# 04_ZYNQ_BANK0.net
KiCad netlist of a schematic drawn in Altium Designer
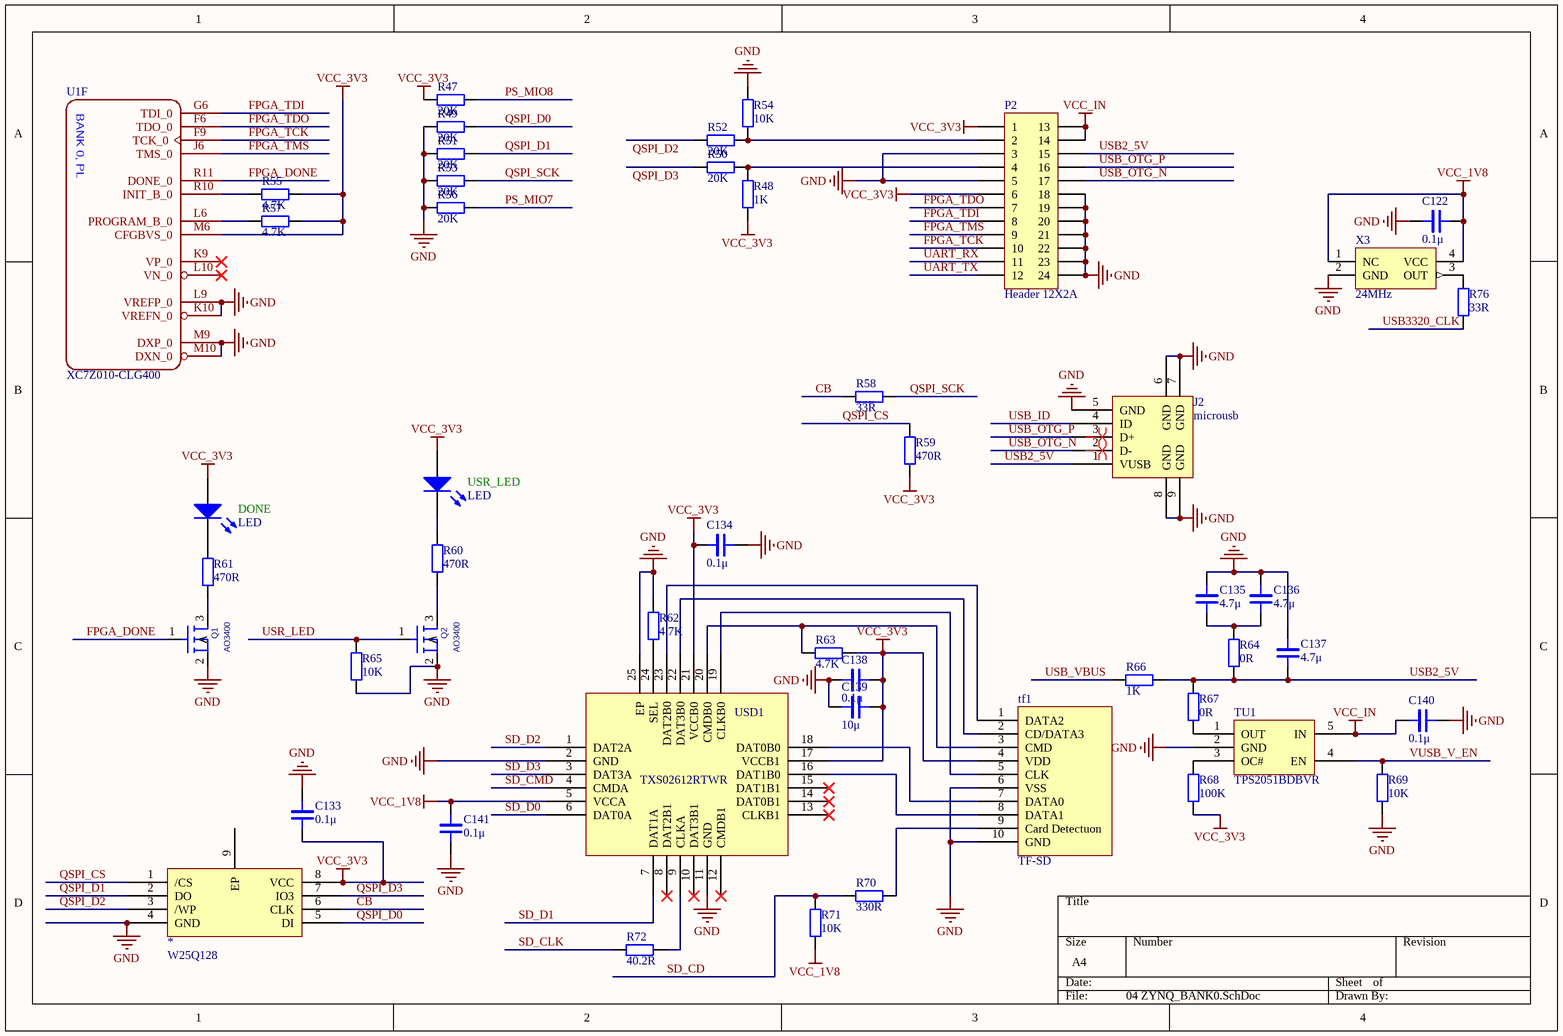
[diagram p0: 04 ZYNQ_BANK0.SchDoc]

(export (version "E")
  (design (tool "Eeschema 10.0.6"))
  (components
    (comp (ref "*") (value "W25Q128") (footprint "W25Q256") (libsource (lib "Schlib1") (part "W25Q128")))
    (comp (ref "C122")
      (value "0.1μ")
      (footprint "LC-0402_C")
      (description "Capacitor")
      (libsource (lib "DDR3_xc7z010-clg400") (part "CAP_2"))
    )
    (comp (ref "C133")
      (value "0.1μ")
      (footprint "LC-0402_C")
      (description "Capacitor")
      (libsource (lib "DDR3_xc7z010-clg400") (part "CAP_2"))
    )
    (comp (ref "C134")
      (value "0.1μ")
      (footprint "LC-0402_C")
      (description "Capacitor")
      (libsource (lib "DDR3_xc7z010-clg400") (part "CAP_2"))
    )
    (comp (ref "C135")
      (value "4.7μ")
      (footprint "LC-0402_C")
      (description "Capacitor")
      (libsource (lib "DDR3_xc7z010-clg400") (part "CAP_2"))
    )
    (comp (ref "C136")
      (value "4.7μ")
      (footprint "LC-0402_C")
      (description "Capacitor")
      (libsource (lib "DDR3_xc7z010-clg400") (part "CAP_2"))
    )
    (comp (ref "C137")
      (value "4.7μ")
      (footprint "LC-0402_C")
      (description "Capacitor")
      (libsource (lib "DDR3_xc7z010-clg400") (part "CAP_2"))
    )
    (comp (ref "C138")
      (value "0.1μ")
      (footprint "LC-0402_C")
      (description "Capacitor")
      (libsource (lib "DDR3_xc7z010-clg400") (part "CAP_2"))
    )
    (comp (ref "C139")
      (value "10μ")
      (footprint "LC-0402_C")
      (description "Capacitor")
      (libsource (lib "DDR3_xc7z010-clg400") (part "CAP_2"))
    )
    (comp (ref "C140")
      (value "0.1μ")
      (footprint "LC-0402_C")
      (description "Capacitor")
      (libsource (lib "DDR3_xc7z010-clg400") (part "CAP_2"))
    )
    (comp (ref "C141")
      (value "0.1μ")
      (footprint "LC-0402_C")
      (description "Capacitor")
      (libsource (lib "DDR3_xc7z010-clg400") (part "CAP_2"))
    )
    (comp (ref "DONE")
      (value "LED")
      (footprint "D0402")
      (description "Typical INFRARED GaAs LED")
      (fields (field (name "PUBLISHER") "Altium Limited"))
      (libsource (lib "Miscellaneous Devices") (part "LED0"))
    )
    (comp (ref "J2")
      (value "microusb")
      (footprint "micro usb")
      (libsource (lib "AD9363_ZYNQ_V2") (part "microusb"))
    )
    (comp (ref "P2")
      (value "Header 12X2A")
      (footprint "HDR2X12_CEN")
      (description "Header, 12-Pin, Dual row")
      (fields (field (name "PUBLISHER") "Altium Limited"))
      (libsource (lib "Miscellaneous Connectors") (part "Header 12X2A"))
    )
    (comp (ref "Q1") (value "AO3400") (footprint "NMOS") (libsource (lib "ZYNQ领航者底板") (part "AO3400")))
    (comp (ref "Q2") (value "AO3400") (footprint "NMOS") (libsource (lib "ZYNQ领航者底板") (part "AO3400")))
    (comp (ref "R47")
      (value "20K")
      (footprint "LC-0402_R")
      (description "Resistor")
      (libsource (lib "") (part "RES_1"))
    )
    (comp (ref "R48")
      (value "1K")
      (footprint "LC-0402_R")
      (description "Resistor")
      (libsource (lib "") (part "RES_3"))
    )
    (comp (ref "R49")
      (value "20K")
      (footprint "LC-0402_R")
      (description "Resistor")
      (libsource (lib "") (part "RES_1"))
    )
    (comp (ref "R50")
      (value "20K")
      (footprint "LC-0402_R")
      (description "Resistor")
      (libsource (lib "") (part "RES_2"))
    )
    (comp (ref "R51")
      (value "20K")
      (footprint "LC-0402_R")
      (description "Resistor")
      (libsource (lib "") (part "RES_1"))
    )
    (comp (ref "R52")
      (value "20K")
      (footprint "LC-0402_R")
      (description "Resistor")
      (libsource (lib "") (part "RES_2"))
    )
    (comp (ref "R53")
      (value "20K")
      (footprint "LC-0402_R")
      (description "Resistor")
      (libsource (lib "") (part "RES_1"))
    )
    (comp (ref "R54")
      (value "10K")
      (footprint "LC-0402_R")
      (description "Resistor")
      (libsource (lib "") (part "RES_3"))
    )
    (comp (ref "R55")
      (value "4.7K")
      (footprint "LC-0402_R")
      (description "Resistor")
      (libsource (lib "") (part "RES_2"))
    )
    (comp (ref "R56")
      (value "20K")
      (footprint "LC-0402_R")
      (description "Resistor")
      (libsource (lib "") (part "RES_1"))
    )
    (comp (ref "R57")
      (value "4.7K")
      (footprint "LC-0402_R")
      (description "Resistor")
      (libsource (lib "") (part "RES_2"))
    )
    (comp (ref "R58")
      (value "33R")
      (footprint "LC-0402_R")
      (description "Resistor")
      (libsource (lib "") (part "RES_1"))
    )
    (comp (ref "R59")
      (value "470R")
      (footprint "LC-0402_R")
      (description "Resistor")
      (libsource (lib "DDR3_xc7z010-clg400") (part "RES"))
    )
    (comp (ref "R60")
      (value "470R")
      (footprint "LC-0402_R")
      (description "Resistor")
      (libsource (lib "") (part "RES_3"))
    )
    (comp (ref "R61")
      (value "470R")
      (footprint "LC-0402_R")
      (description "Resistor")
      (libsource (lib "") (part "RES_3"))
    )
    (comp (ref "R62")
      (value "4.7K")
      (footprint "LC-0402_R")
      (description "Resistor")
      (libsource (lib "DDR3_xc7z010-clg400") (part "RES"))
    )
    (comp (ref "R63")
      (value "4.7K")
      (footprint "LC-0402_R")
      (description "Resistor")
      (libsource (lib "") (part "RES_2"))
    )
    (comp (ref "R64")
      (value "0R")
      (footprint "LC-0402_R")
      (description "Resistor")
      (libsource (lib "DDR3_xc7z010-clg400") (part "RES"))
    )
    (comp (ref "R65")
      (value "10K")
      (footprint "LC-0402_R")
      (description "Resistor")
      (libsource (lib "DDR3_xc7z010-clg400") (part "RES"))
    )
    (comp (ref "R66")
      (value "1K")
      (footprint "LC-0402_R")
      (description "Resistor")
      (libsource (lib "") (part "RES_2"))
    )
    (comp (ref "R67")
      (value "0R")
      (footprint "LC-0402_R")
      (description "Resistor")
      (libsource (lib "DDR3_xc7z010-clg400") (part "RES"))
    )
    (comp (ref "R68")
      (value "100K")
      (footprint "LC-0402_R")
      (description "Resistor")
      (libsource (lib "DDR3_xc7z010-clg400") (part "RES"))
    )
    (comp (ref "R69")
      (value "10K")
      (footprint "LC-0402_R")
      (description "Resistor")
      (libsource (lib "DDR3_xc7z010-clg400") (part "RES"))
    )
    (comp (ref "R70")
      (value "330R")
      (footprint "LC-0402_R")
      (description "Resistor")
      (libsource (lib "") (part "RES_2"))
    )
    (comp (ref "R71")
      (value "10K")
      (footprint "LC-0402_R")
      (description "Resistor")
      (libsource (lib "DDR3_xc7z010-clg400") (part "RES"))
    )
    (comp (ref "R72")
      (value "40.2R")
      (footprint "LC-0402_R")
      (description "Resistor")
      (libsource (lib "") (part "RES_2"))
    )
    (comp (ref "R76")
      (value "33R")
      (footprint "LC-0402_R")
      (description "Resistor")
      (libsource (lib "") (part "RES_3"))
    )
    (comp (ref "tf1") (value "TF-SD") (footprint "TF") (libsource (lib "PCB_Project") (part "TF-SD")))
    (comp (ref "TU1")
      (value "TPS2051BDBVR")
      (footprint "TPS2051BDBVR")
      (libsource (lib "Schlib1") (part "TPS2051BDBVR"))
    )
    (comp (ref "U1")
      (value "XC7Z010-CLG400")
      (footprint "CLG400-0.8")
      (libsource (lib "DDR3_xc7z010-clg400") (part "XC7Z010-CLG400"))
    )
    (comp (ref "USD1")
      (value "TXS02612RTWR")
      (footprint "TXS02612RTWR")
      (libsource (lib "Schlib1") (part "TXS02612RTWR"))
    )
    (comp (ref "USR_LED")
      (value "LED")
      (footprint "D0402")
      (description "Typical INFRARED GaAs LED")
      (fields (field (name "PUBLISHER") "Altium Limited"))
      (libsource (lib "Miscellaneous Devices") (part "LED0"))
    )
    (comp (ref "X3")
      (value "24MHz")
      (footprint "OSC-SMD_4P-L3.2-W2.5-BL")
      (description "Oscillator")
      (libsource (lib "DDR3_xc7z010-clg400") (part "XTAL-4"))
    )
  )
  (nets
    (net (code "1") (name "/CB") (class "Default")
      (node (ref "*") (pin "6") (pinfunction "CLK_6") (pintype "passive"))
      (node (ref "R58") (pin "1") (pinfunction "1_1") (pintype "passive"))
    )
    (net (code "2") (name "/FPGA_DONE") (class "Default")
      (node (ref "Q1") (pin "1") (pinfunction "G_1") (pintype "passive"))
      (node (ref "U1") (pin "R11") (pinfunction "DONE_0_R11") (pintype "passive"))
    )
    (net (code "3") (name "/FPGA_TCK") (class "Default")
      (node (ref "P2") (pin "10") (pinfunction "10_10") (pintype "passive"))
      (node (ref "U1") (pin "F9") (pinfunction "TCK_0_F9") (pintype "passive"))
    )
    (net (code "4") (name "/FPGA_TDI") (class "Default")
      (node (ref "P2") (pin "8") (pinfunction "8_8") (pintype "passive"))
      (node (ref "U1") (pin "G6") (pinfunction "TDI_0_G6") (pintype "passive"))
    )
    (net (code "5") (name "/FPGA_TDO") (class "Default")
      (node (ref "P2") (pin "7") (pinfunction "7_7") (pintype "passive"))
      (node (ref "U1") (pin "F6") (pinfunction "TDO_0_F6") (pintype "passive"))
    )
    (net (code "6") (name "/FPGA_TMS") (class "Default")
      (node (ref "P2") (pin "9") (pinfunction "9_9") (pintype "passive"))
      (node (ref "U1") (pin "J6") (pinfunction "TMS_0_J6") (pintype "passive"))
    )
    (net (code "7") (name "/PS_MIO7") (class "Default")
      (node (ref "R56") (pin "2") (pinfunction "2_2") (pintype "passive"))
    )
    (net (code "8") (name "/PS_MIO8") (class "Default")
      (node (ref "R47") (pin "2") (pinfunction "2_2") (pintype "passive"))
    )
    (net (code "9") (name "/QSPI_CS") (class "Default")
      (node (ref "*") (pin "1") (pinfunction "/CS_1") (pintype "passive"))
      (node (ref "R59") (pin "1") (pinfunction "1_1") (pintype "passive"))
    )
    (net (code "10") (name "/QSPI_D0") (class "Default")
      (node (ref "*") (pin "5") (pinfunction "DI_5") (pintype "passive"))
      (node (ref "R49") (pin "2") (pinfunction "2_2") (pintype "passive"))
    )
    (net (code "11") (name "/QSPI_D1") (class "Default")
      (node (ref "*") (pin "2") (pinfunction "DO_2") (pintype "passive"))
      (node (ref "R51") (pin "2") (pinfunction "2_2") (pintype "passive"))
    )
    (net (code "12") (name "/QSPI_D2") (class "Default")
      (node (ref "*") (pin "3") (pinfunction "/WP_3") (pintype "passive"))
      (node (ref "R52") (pin "2") (pinfunction "2_2") (pintype "passive"))
    )
    (net (code "13") (name "/QSPI_D3") (class "Default")
      (node (ref "*") (pin "7") (pinfunction "IO3_7") (pintype "passive"))
      (node (ref "R50") (pin "2") (pinfunction "2_2") (pintype "passive"))
    )
    (net (code "14") (name "/QSPI_SCK") (class "Default")
      (node (ref "R53") (pin "2") (pinfunction "2_2") (pintype "passive"))
      (node (ref "R58") (pin "2") (pinfunction "2_2") (pintype "passive"))
    )
    (net (code "15") (name "/SD_CD") (class "Default")
      (node (ref "R70") (pin "2") (pinfunction "2_2") (pintype "passive"))
      (node (ref "R71") (pin "1") (pinfunction "1_1") (pintype "passive"))
    )
    (net (code "16") (name "/SD_CLK") (class "Default")
      (node (ref "R72") (pin "2") (pinfunction "2_2") (pintype "passive"))
    )
    (net (code "17") (name "/SD_CMD") (class "Default")
      (node (ref "USD1") (pin "4") (pinfunction "CMDA_4") (pintype "passive"))
    )
    (net (code "18") (name "/SD_D0") (class "Default")
      (node (ref "USD1") (pin "6") (pinfunction "DAT0A_6") (pintype "passive"))
    )
    (net (code "19") (name "/SD_D1") (class "Default")
      (node (ref "USD1") (pin "7") (pinfunction "DAT1A_7") (pintype "passive"))
    )
    (net (code "20") (name "/SD_D2") (class "Default")
      (node (ref "USD1") (pin "1") (pinfunction "DAT2A_1") (pintype "passive"))
    )
    (net (code "21") (name "/SD_D3") (class "Default")
      (node (ref "USD1") (pin "3") (pinfunction "DAT3A_3") (pintype "passive"))
    )
    (net (code "22") (name "/UART_RX") (class "Default")
      (node (ref "P2") (pin "11") (pinfunction "11_11") (pintype "passive"))
    )
    (net (code "23") (name "/UART_TX") (class "Default")
      (node (ref "P2") (pin "12") (pinfunction "12_12") (pintype "passive"))
    )
    (net (code "24") (name "/USB2_5V") (class "Default")
      (node (ref "C137") (pin "1") (pinfunction "1_1") (pintype "passive"))
      (node (ref "J2") (pin "1") (pinfunction "VUSB_1") (pintype "passive"))
      (node (ref "P2") (pin "15") (pinfunction "15_15") (pintype "passive"))
      (node (ref "R64") (pin "2") (pinfunction "2_2") (pintype "passive"))
      (node (ref "R66") (pin "1") (pinfunction "1_1") (pintype "passive"))
      (node (ref "R67") (pin "1") (pinfunction "1_1") (pintype "passive"))
    )
    (net (code "25") (name "/USB3320_CLK") (class "Default")
      (node (ref "R76") (pin "1") (pinfunction "1_1") (pintype "passive"))
    )
    (net (code "26") (name "/USB_ID") (class "Default")
      (node (ref "J2") (pin "4") (pinfunction "ID_4") (pintype "passive"))
    )
    (net (code "27") (name "/USB_OTG_N") (class "Default")
      (node (ref "J2") (pin "2") (pinfunction "D-_2") (pintype "passive"))
      (node (ref "P2") (pin "17") (pinfunction "17_17") (pintype "passive"))
    )
    (net (code "28") (name "/USB_OTG_P") (class "Default")
      (node (ref "J2") (pin "3") (pinfunction "D+_3") (pintype "passive"))
      (node (ref "P2") (pin "16") (pinfunction "16_16") (pintype "passive"))
    )
    (net (code "29") (name "/USB_VBUS") (class "Default")
      (node (ref "R66") (pin "2") (pinfunction "2_2") (pintype "passive"))
    )
    (net (code "30") (name "/USR_LED") (class "Default")
      (node (ref "Q2") (pin "1") (pinfunction "G_1") (pintype "passive"))
      (node (ref "R65") (pin "1") (pinfunction "1_1") (pintype "passive"))
    )
    (net (code "31") (name "/VUSB_V_EN") (class "Default")
      (node (ref "R69") (pin "1") (pinfunction "1_1") (pintype "passive"))
      (node (ref "TU1") (pin "4") (pinfunction "EN_4") (pintype "passive"))
    )
    (net (code "32") (name "GND") (class "Default")
      (node (ref "*") (pin "4") (pinfunction "GND_4") (pintype "passive"))
      (node (ref "C122") (pin "2") (pinfunction "2_2") (pintype "passive"))
      (node (ref "C133") (pin "2") (pinfunction "2_2") (pintype "passive"))
      (node (ref "C134") (pin "2") (pinfunction "2_2") (pintype "passive"))
      (node (ref "C135") (pin "2") (pinfunction "2_2") (pintype "passive"))
      (node (ref "C136") (pin "2") (pinfunction "2_2") (pintype "passive"))
      (node (ref "C137") (pin "2") (pinfunction "2_2") (pintype "passive"))
      (node (ref "C138") (pin "2") (pinfunction "2_2") (pintype "passive"))
      (node (ref "C139") (pin "2") (pinfunction "2_2") (pintype "passive"))
      (node (ref "C140") (pin "1") (pinfunction "1_1") (pintype "passive"))
      (node (ref "C141") (pin "2") (pinfunction "2_2") (pintype "passive"))
      (node (ref "J2") (pin "5") (pinfunction "GND_5") (pintype "passive"))
      (node (ref "J2") (pin "6") (pinfunction "GND_6") (pintype "passive"))
      (node (ref "J2") (pin "7") (pinfunction "GND_7") (pintype "passive"))
      (node (ref "J2") (pin "8") (pinfunction "GND_8") (pintype "passive"))
      (node (ref "J2") (pin "9") (pinfunction "GND_9") (pintype "passive"))
      (node (ref "P2") (pin "18") (pinfunction "18_18") (pintype "passive"))
      (node (ref "P2") (pin "19") (pinfunction "19_19") (pintype "passive"))
      (node (ref "P2") (pin "20") (pinfunction "20_20") (pintype "passive"))
      (node (ref "P2") (pin "21") (pinfunction "21_21") (pintype "passive"))
      (node (ref "P2") (pin "22") (pinfunction "22_22") (pintype "passive"))
      (node (ref "P2") (pin "23") (pinfunction "23_23") (pintype "passive"))
      (node (ref "P2") (pin "24") (pinfunction "24_24") (pintype "passive"))
      (node (ref "P2") (pin "3") (pinfunction "3_3") (pintype "passive"))
      (node (ref "P2") (pin "5") (pinfunction "5_5") (pintype "passive"))
      (node (ref "Q1") (pin "2") (pinfunction "S_2") (pintype "passive"))
      (node (ref "Q2") (pin "2") (pinfunction "S_2") (pintype "passive"))
      (node (ref "R49") (pin "1") (pinfunction "1_1") (pintype "passive"))
      (node (ref "R51") (pin "1") (pinfunction "1_1") (pintype "passive"))
      (node (ref "R53") (pin "1") (pinfunction "1_1") (pintype "passive"))
      (node (ref "R54") (pin "2") (pinfunction "2_2") (pintype "passive"))
      (node (ref "R56") (pin "1") (pinfunction "1_1") (pintype "passive"))
      (node (ref "R62") (pin "1") (pinfunction "1_1") (pintype "passive"))
      (node (ref "R65") (pin "2") (pinfunction "2_2") (pintype "passive"))
      (node (ref "R69") (pin "2") (pinfunction "2_2") (pintype "passive"))
      (node (ref "TU1") (pin "2") (pinfunction "GND_2") (pintype "passive"))
      (node (ref "U1") (pin "K10") (pinfunction "VREFN_0_K10") (pintype "passive"))
      (node (ref "U1") (pin "L9") (pinfunction "VREFP_0_L9") (pintype "passive"))
      (node (ref "U1") (pin "M10") (pinfunction "DXN_0_M10") (pintype "passive"))
      (node (ref "U1") (pin "M9") (pinfunction "DXP_0_M9") (pintype "passive"))
      (node (ref "USD1") (pin "11") (pinfunction "GND_11") (pintype "passive"))
      (node (ref "USD1") (pin "2") (pinfunction "GND_2") (pintype "passive"))
      (node (ref "USD1") (pin "25") (pinfunction "EP_25") (pintype "passive"))
      (node (ref "X3") (pin "2") (pinfunction "GND_2") (pintype "power_in"))
      (node (ref "tf1") (pin "10") (pinfunction "GND_10") (pintype "passive"))
      (node (ref "tf1") (pin "6") (pinfunction "VSS_6") (pintype "passive"))
    )
    (net (code "33") (name "Net-(C135-Pad1)") (class "Default")
      (node (ref "C135") (pin "1") (pinfunction "1_1") (pintype "passive"))
      (node (ref "C136") (pin "1") (pinfunction "1_1") (pintype "passive"))
      (node (ref "R64") (pin "1") (pinfunction "1_1") (pintype "passive"))
    )
    (net (code "34") (name "Net-(DONE-K)") (class "Default")
      (node (ref "DONE") (pin "2") (pinfunction "K_2") (pintype "passive"))
      (node (ref "R61") (pin "2") (pinfunction "2_2") (pintype "passive"))
    )
    (net (code "35") (name "Net-(P2-Pad2)") (class "Default")
      (node (ref "P2") (pin "2") (pinfunction "2_2") (pintype "passive"))
      (node (ref "R52") (pin "1") (pinfunction "1_1") (pintype "passive"))
      (node (ref "R54") (pin "1") (pinfunction "1_1") (pintype "passive"))
    )
    (net (code "36") (name "Net-(P2-Pad4)") (class "Default")
      (node (ref "P2") (pin "4") (pinfunction "4_4") (pintype "passive"))
      (node (ref "R48") (pin "2") (pinfunction "2_2") (pintype "passive"))
      (node (ref "R50") (pin "1") (pinfunction "1_1") (pintype "passive"))
    )
    (net (code "37") (name "Net-(Q1-D)") (class "Default")
      (node (ref "Q1") (pin "3") (pinfunction "D_3") (pintype "passive"))
      (node (ref "R61") (pin "1") (pinfunction "1_1") (pintype "passive"))
    )
    (net (code "38") (name "Net-(Q2-D)") (class "Default")
      (node (ref "Q2") (pin "3") (pinfunction "D_3") (pintype "passive"))
      (node (ref "R60") (pin "1") (pinfunction "1_1") (pintype "passive"))
    )
    (net (code "39") (name "Net-(TU1-OC#)") (class "Default")
      (node (ref "R68") (pin "1") (pinfunction "1_1") (pintype "passive"))
      (node (ref "TU1") (pin "3") (pinfunction "OC#_3") (pintype "passive"))
    )
    (net (code "40") (name "Net-(TU1-OUT)") (class "Default")
      (node (ref "R67") (pin "2") (pinfunction "2_2") (pintype "passive"))
      (node (ref "TU1") (pin "1") (pinfunction "OUT_1") (pintype "passive"))
    )
    (net (code "41") (name "Net-(U1F-INIT_B_0)") (class "Default")
      (node (ref "R55") (pin "2") (pinfunction "2_2") (pintype "passive"))
      (node (ref "U1") (pin "R10") (pinfunction "INIT_B_0_R10") (pintype "passive"))
    )
    (net (code "42") (name "Net-(U1F-PROGRAM_B_0)") (class "Default")
      (node (ref "R57") (pin "2") (pinfunction "2_2") (pintype "passive"))
      (node (ref "U1") (pin "L6") (pinfunction "PROGRAM_B_0_L6") (pintype "passive"))
    )
    (net (code "43") (name "Net-(USD1-CLKA)") (class "Default")
      (node (ref "R72") (pin "1") (pinfunction "1_1") (pintype "passive"))
      (node (ref "USD1") (pin "9") (pinfunction "CLKA_9") (pintype "passive"))
    )
    (net (code "44") (name "Net-(USD1-CLKB0)") (class "Default")
      (node (ref "USD1") (pin "19") (pinfunction "CLKB0_19") (pintype "passive"))
      (node (ref "tf1") (pin "5") (pinfunction "CLK_5") (pintype "passive"))
    )
    (net (code "45") (name "Net-(USD1-CMDB0)") (class "Default")
      (node (ref "R63") (pin "2") (pinfunction "2_2") (pintype "passive"))
      (node (ref "USD1") (pin "20") (pinfunction "CMDB0_20") (pintype "passive"))
      (node (ref "tf1") (pin "3") (pinfunction "CMD_3") (pintype "passive"))
    )
    (net (code "46") (name "Net-(USD1-DAT0B0)") (class "Default")
      (node (ref "USD1") (pin "18") (pinfunction "DAT0B0_18") (pintype "passive"))
      (node (ref "tf1") (pin "7") (pinfunction "DATA0_7") (pintype "passive"))
    )
    (net (code "47") (name "Net-(USD1-DAT1B0)") (class "Default")
      (node (ref "USD1") (pin "16") (pinfunction "DAT1B0_16") (pintype "passive"))
      (node (ref "tf1") (pin "8") (pinfunction "DATA1_8") (pintype "passive"))
    )
    (net (code "48") (name "Net-(USD1-DAT2B0)") (class "Default")
      (node (ref "USD1") (pin "23") (pinfunction "DAT2B0_23") (pintype "passive"))
      (node (ref "tf1") (pin "1") (pinfunction "DATA2_1") (pintype "passive"))
    )
    (net (code "49") (name "Net-(USD1-DAT3B0)") (class "Default")
      (node (ref "USD1") (pin "22") (pinfunction "DAT3B0_22") (pintype "passive"))
      (node (ref "tf1") (pin "2") (pinfunction "CD/DATA3_2") (pintype "passive"))
    )
    (net (code "50") (name "Net-(USD1-SEL)") (class "Default")
      (node (ref "R62") (pin "2") (pinfunction "2_2") (pintype "passive"))
      (node (ref "USD1") (pin "24") (pinfunction "SEL_24") (pintype "passive"))
    )
    (net (code "51") (name "Net-(USR_LED-K)") (class "Default")
      (node (ref "R60") (pin "2") (pinfunction "2_2") (pintype "passive"))
      (node (ref "USR_LED") (pin "2") (pinfunction "K_2") (pintype "passive"))
    )
    (net (code "52") (name "Net-(X3-OUT)") (class "Default")
      (node (ref "R76") (pin "2") (pinfunction "2_2") (pintype "passive"))
      (node (ref "X3") (pin "3") (pinfunction "OUT_3") (pintype "output"))
    )
    (net (code "53") (name "Net-(tf1-Card_Detectuon)") (class "Default")
      (node (ref "R70") (pin "1") (pinfunction "1_1") (pintype "passive"))
      (node (ref "tf1") (pin "9") (pinfunction "Card_Detectuon_9") (pintype "passive"))
    )
    (net (code "54") (name "VCC_1V8") (class "Default")
      (node (ref "C122") (pin "1") (pinfunction "1_1") (pintype "passive"))
      (node (ref "C141") (pin "1") (pinfunction "1_1") (pintype "passive"))
      (node (ref "R71") (pin "2") (pinfunction "2_2") (pintype "passive"))
      (node (ref "USD1") (pin "5") (pinfunction "VCCA_5") (pintype "passive"))
      (node (ref "X3") (pin "1") (pinfunction "NC_1") (pintype "passive"))
      (node (ref "X3") (pin "4") (pinfunction "VCC_4") (pintype "power_in"))
    )
    (net (code "55") (name "VCC_3V3") (class "Default")
      (node (ref "*") (pin "8") (pinfunction "VCC_8") (pintype "passive"))
      (node (ref "C133") (pin "1") (pinfunction "1_1") (pintype "passive"))
      (node (ref "C134") (pin "1") (pinfunction "1_1") (pintype "passive"))
      (node (ref "C138") (pin "1") (pinfunction "1_1") (pintype "passive"))
      (node (ref "C139") (pin "1") (pinfunction "1_1") (pintype "passive"))
      (node (ref "DONE") (pin "1") (pinfunction "A_1") (pintype "passive"))
      (node (ref "P2") (pin "1") (pinfunction "1_1") (pintype "passive"))
      (node (ref "P2") (pin "6") (pinfunction "6_6") (pintype "passive"))
      (node (ref "R47") (pin "1") (pinfunction "1_1") (pintype "passive"))
      (node (ref "R48") (pin "1") (pinfunction "1_1") (pintype "passive"))
      (node (ref "R55") (pin "1") (pinfunction "1_1") (pintype "passive"))
      (node (ref "R57") (pin "1") (pinfunction "1_1") (pintype "passive"))
      (node (ref "R59") (pin "2") (pinfunction "2_2") (pintype "passive"))
      (node (ref "R63") (pin "1") (pinfunction "1_1") (pintype "passive"))
      (node (ref "R68") (pin "2") (pinfunction "2_2") (pintype "passive"))
      (node (ref "U1") (pin "M6") (pinfunction "CFGBVS_0_M6") (pintype "passive"))
      (node (ref "USD1") (pin "17") (pinfunction "VCCB1_17") (pintype "passive"))
      (node (ref "USD1") (pin "21") (pinfunction "VCCB0_21") (pintype "passive"))
      (node (ref "USR_LED") (pin "1") (pinfunction "A_1") (pintype "passive"))
      (node (ref "tf1") (pin "4") (pinfunction "VDD_4") (pintype "passive"))
    )
    (net (code "56") (name "VCC_IN") (class "Default")
      (node (ref "C140") (pin "2") (pinfunction "2_2") (pintype "passive"))
      (node (ref "P2") (pin "13") (pinfunction "13_13") (pintype "passive"))
      (node (ref "P2") (pin "14") (pinfunction "14_14") (pintype "passive"))
      (node (ref "TU1") (pin "5") (pinfunction "IN_5") (pintype "passive"))
    )
    (net (code "57") (name "unconnected-(*-EP-Pad9)") (class "Default")
      (node (ref "*") (pin "9") (pinfunction "EP_9") (pintype "passive"))
    )
    (net (code "58") (name "unconnected-(U1F-VN_0-PadL10)") (class "Default")
      (node (ref "U1") (pin "L10") (pinfunction "VN_0_L10") (pintype "passive+no_connect"))
    )
    (net (code "59") (name "unconnected-(U1F-VP_0-PadK9)") (class "Default")
      (node (ref "U1") (pin "K9") (pinfunction "VP_0_K9") (pintype "passive+no_connect"))
    )
    (net (code "60") (name "unconnected-(USD1-CLKB1-Pad13)") (class "Default")
      (node (ref "USD1") (pin "13") (pinfunction "CLKB1_13") (pintype "passive+no_connect"))
    )
    (net (code "61") (name "unconnected-(USD1-CMDB1-Pad12)") (class "Default")
      (node (ref "USD1") (pin "12") (pinfunction "CMDB1_12") (pintype "passive+no_connect"))
    )
    (net (code "62") (name "unconnected-(USD1-DAT0B1-Pad14)") (class "Default")
      (node (ref "USD1") (pin "14") (pinfunction "DAT0B1_14") (pintype "passive+no_connect"))
    )
    (net (code "63") (name "unconnected-(USD1-DAT1B1-Pad15)") (class "Default")
      (node (ref "USD1") (pin "15") (pinfunction "DAT1B1_15") (pintype "passive+no_connect"))
    )
    (net (code "64") (name "unconnected-(USD1-DAT2B1-Pad8)") (class "Default")
      (node (ref "USD1") (pin "8") (pinfunction "DAT2B1_8") (pintype "passive+no_connect"))
    )
    (net (code "65") (name "unconnected-(USD1-DAT3B1-Pad10)") (class "Default")
      (node (ref "USD1") (pin "10") (pinfunction "DAT3B1_10") (pintype "passive+no_connect"))
    )
  )
)
